# STM8L-FOX_80m_CNTL_V5_3.net
KiCad netlist of a schematic drawn in EAGLE
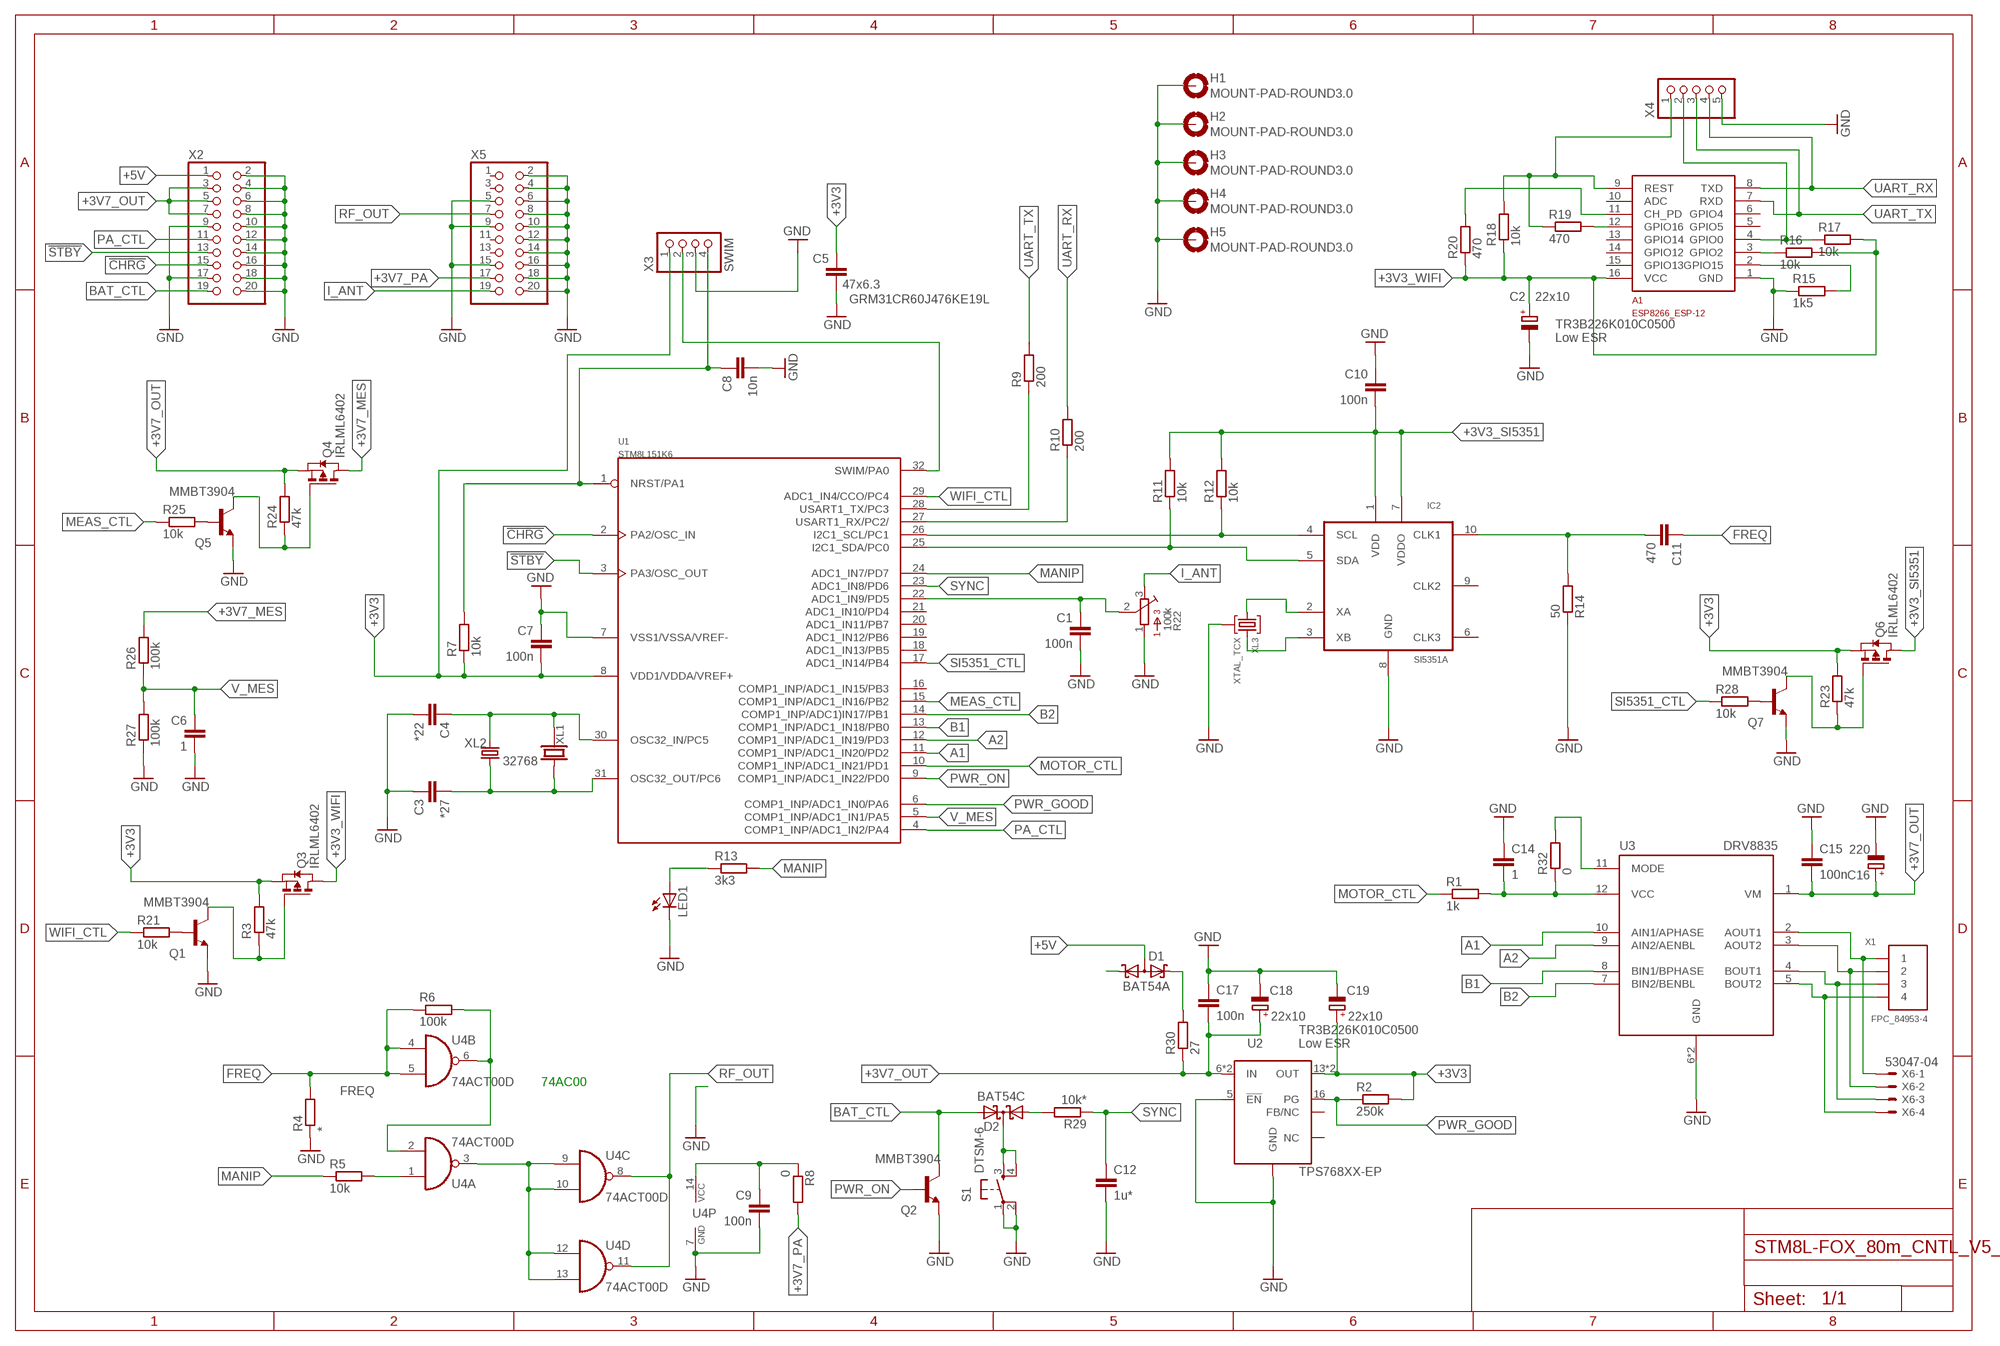
[diagram p0: schematic, sheet 1]

(export (version "E")
  (design (tool "Eeschema 10.0.6"))
  (components
    (comp (ref "A1")
      (value "ESP8266_ESP-12")
      (footprint "eagle-import:ESP8266-ESP12")
      (libsource (lib "eagle-import") (part "ESP8266_ESP-12"))
    )
    (comp (ref "C1")
      (value "100n")
      (footprint "eagle-import:C1206K")
      (libsource (lib "eagle-import") (part "C-EUC1206K"))
    )
    (comp (ref "C2")
      (value "22x10")
      (footprint "eagle-import:B_3528-21W")
      (libsource (lib "eagle-import") (part "CPOL-EUB/3528-21W"))
    )
    (comp (ref "C3")
      (value "*27")
      (footprint "eagle-import:C0805K")
      (libsource (lib "eagle-import") (part "C-EUC0805K"))
    )
    (comp (ref "C4")
      (value "*22")
      (footprint "eagle-import:C0805K")
      (libsource (lib "eagle-import") (part "C-EUC0805K"))
    )
    (comp (ref "C5")
      (value "47x6.3")
      (footprint "eagle-import:C1206K")
      (libsource (lib "eagle-import") (part "C-EUC1206K"))
    )
    (comp (ref "C6")
      (value "1")
      (footprint "eagle-import:C1206K")
      (libsource (lib "eagle-import") (part "C-EUC1206K"))
    )
    (comp (ref "C7")
      (value "100n")
      (footprint "eagle-import:C1206K")
      (libsource (lib "eagle-import") (part "C-EUC1206K"))
    )
    (comp (ref "C8")
      (value "10n")
      (footprint "eagle-import:C0805K")
      (libsource (lib "eagle-import") (part "C-EUC0805K"))
    )
    (comp (ref "C9")
      (value "100n")
      (footprint "eagle-import:C1206K")
      (libsource (lib "eagle-import") (part "C-EUC1206K"))
    )
    (comp (ref "C10")
      (value "100n")
      (footprint "eagle-import:C1206K")
      (libsource (lib "eagle-import") (part "C-EUC1206K"))
    )
    (comp (ref "C11")
      (value "470")
      (footprint "eagle-import:C1206K")
      (libsource (lib "eagle-import") (part "C-EUC1206K"))
    )
    (comp (ref "C12")
      (value "1u*")
      (footprint "eagle-import:C1206K")
      (libsource (lib "eagle-import") (part "C-EUC1206K"))
    )
    (comp (ref "C14")
      (value "1")
      (footprint "eagle-import:C1206K")
      (libsource (lib "eagle-import") (part "C-EUC1206K"))
    )
    (comp (ref "C15")
      (value "100n")
      (footprint "eagle-import:C1206K")
      (libsource (lib "eagle-import") (part "C-EUC1206K"))
    )
    (comp (ref "C16")
      (value "220")
      (footprint "eagle-import:C_6032-28R")
      (libsource (lib "eagle-import") (part "CPOL-EUC/6032-28R"))
    )
    (comp (ref "C17")
      (value "100n")
      (footprint "eagle-import:C1206K")
      (libsource (lib "eagle-import") (part "C-EUC1206K"))
    )
    (comp (ref "C18")
      (value "22x10")
      (footprint "eagle-import:B_3528-21W")
      (libsource (lib "eagle-import") (part "CPOL-EUB/3528-21W"))
    )
    (comp (ref "C19")
      (value "22x10")
      (footprint "eagle-import:B_3528-21W")
      (libsource (lib "eagle-import") (part "CPOL-EUB/3528-21W"))
    )
    (comp (ref "D1")
      (value "BAT54A")
      (footprint "eagle-import:SOT23")
      (libsource (lib "eagle-import") (part "BAT54A"))
    )
    (comp (ref "D2")
      (value "BAT54C")
      (footprint "eagle-import:SOT23")
      (libsource (lib "eagle-import") (part "BAT54C"))
    )
    (comp (ref "H1")
      (value "MOUNT-PAD-ROUND3.0")
      (footprint "eagle-import:3,0-PAD")
      (libsource (lib "eagle-import") (part "MOUNT-PAD-ROUND3.0"))
    )
    (comp (ref "H2")
      (value "MOUNT-PAD-ROUND3.0")
      (footprint "eagle-import:3,0-PAD")
      (libsource (lib "eagle-import") (part "MOUNT-PAD-ROUND3.0"))
    )
    (comp (ref "H3")
      (value "MOUNT-PAD-ROUND3.0")
      (footprint "eagle-import:3,0-PAD")
      (libsource (lib "eagle-import") (part "MOUNT-PAD-ROUND3.0"))
    )
    (comp (ref "H4")
      (value "MOUNT-PAD-ROUND3.0")
      (footprint "eagle-import:3,0-PAD")
      (libsource (lib "eagle-import") (part "MOUNT-PAD-ROUND3.0"))
    )
    (comp (ref "H5")
      (value "MOUNT-PAD-ROUND3.0")
      (footprint "eagle-import:3,0-PAD")
      (libsource (lib "eagle-import") (part "MOUNT-PAD-ROUND3.0"))
    )
    (comp (ref "IC2")
      (value "SI5351A")
      (footprint "eagle-import:MSOP10")
      (libsource (lib "eagle-import") (part "SI5351A"))
    )
    (comp (ref "LED1")
      (value "LED3MM")
      (footprint "eagle-import:LED3MM")
      (libsource (lib "eagle-import") (part "LED3MM"))
    )
    (comp (ref "Q1")
      (value "MMBT3904")
      (footprint "eagle-import:SOT23-BEC")
      (libsource (lib "eagle-import") (part "-NPN-SOT23-BECMMBT3904LT1"))
    )
    (comp (ref "Q2")
      (value "MMBT3904")
      (footprint "eagle-import:SOT23-BEC")
      (libsource (lib "eagle-import") (part "-NPN-SOT23-BECMMBT3904LT1"))
    )
    (comp (ref "Q3")
      (value "IRLML6402")
      (footprint "eagle-import:SOT-23")
      (libsource (lib "eagle-import") (part "IRLML6402"))
    )
    (comp (ref "Q4")
      (value "IRLML6402")
      (footprint "eagle-import:SOT-23")
      (libsource (lib "eagle-import") (part "IRLML6402"))
    )
    (comp (ref "Q5")
      (value "MMBT3904")
      (footprint "eagle-import:SOT23-BEC")
      (libsource (lib "eagle-import") (part "-NPN-SOT23-BECMMBT3904LT1"))
    )
    (comp (ref "Q6")
      (value "IRLML6402")
      (footprint "eagle-import:SOT-23")
      (libsource (lib "eagle-import") (part "IRLML6402"))
    )
    (comp (ref "Q7")
      (value "MMBT3904")
      (footprint "eagle-import:SOT23-BEC")
      (libsource (lib "eagle-import") (part "-NPN-SOT23-BECMMBT3904LT1"))
    )
    (comp (ref "R1")
      (value "1k")
      (footprint "eagle-import:R1206")
      (libsource (lib "eagle-import") (part "R-EU_R1206"))
    )
    (comp (ref "R2")
      (value "250k")
      (footprint "eagle-import:R1206")
      (libsource (lib "eagle-import") (part "R-EU_R1206"))
    )
    (comp (ref "R3")
      (value "47k")
      (footprint "eagle-import:R1206")
      (libsource (lib "eagle-import") (part "R-EU_R1206"))
    )
    (comp (ref "R4")
      (value "*")
      (footprint "eagle-import:R1206")
      (libsource (lib "eagle-import") (part "R-EU_R1206"))
    )
    (comp (ref "R5")
      (value "10k")
      (footprint "eagle-import:R1206")
      (libsource (lib "eagle-import") (part "R-EU_R1206"))
    )
    (comp (ref "R6")
      (value "100k")
      (footprint "eagle-import:R1206")
      (libsource (lib "eagle-import") (part "R-EU_R1206"))
    )
    (comp (ref "R7")
      (value "10k")
      (footprint "eagle-import:R1206")
      (libsource (lib "eagle-import") (part "R-EU_R1206"))
    )
    (comp (ref "R8")
      (value "0")
      (footprint "eagle-import:R1206")
      (libsource (lib "eagle-import") (part "R-EU_R1206"))
    )
    (comp (ref "R9")
      (value "200")
      (footprint "eagle-import:R1206")
      (libsource (lib "eagle-import") (part "R-EU_R1206"))
    )
    (comp (ref "R10")
      (value "200")
      (footprint "eagle-import:R1206")
      (libsource (lib "eagle-import") (part "R-EU_R1206"))
    )
    (comp (ref "R11")
      (value "10k")
      (footprint "eagle-import:R1206")
      (libsource (lib "eagle-import") (part "R-EU_R1206"))
    )
    (comp (ref "R12")
      (value "10k")
      (footprint "eagle-import:R1206")
      (libsource (lib "eagle-import") (part "R-EU_R1206"))
    )
    (comp (ref "R13")
      (value "3k3")
      (footprint "eagle-import:R1206")
      (libsource (lib "eagle-import") (part "R-EU_R1206"))
    )
    (comp (ref "R14")
      (value "50")
      (footprint "eagle-import:R1206")
      (libsource (lib "eagle-import") (part "R-EU_R1206"))
    )
    (comp (ref "R15")
      (value "1k5")
      (footprint "eagle-import:R1206")
      (libsource (lib "eagle-import") (part "R-EU_R1206"))
    )
    (comp (ref "R16")
      (value "10k")
      (footprint "eagle-import:R1206")
      (libsource (lib "eagle-import") (part "R-EU_R1206"))
    )
    (comp (ref "R17")
      (value "10k")
      (footprint "eagle-import:R1206")
      (libsource (lib "eagle-import") (part "R-EU_R1206"))
    )
    (comp (ref "R18")
      (value "10k")
      (footprint "eagle-import:R1206")
      (libsource (lib "eagle-import") (part "R-EU_R1206"))
    )
    (comp (ref "R19")
      (value "470")
      (footprint "eagle-import:R1206")
      (libsource (lib "eagle-import") (part "R-EU_R1206"))
    )
    (comp (ref "R20")
      (value "470")
      (footprint "eagle-import:R1206")
      (libsource (lib "eagle-import") (part "R-EU_R1206"))
    )
    (comp (ref "R21")
      (value "10k")
      (footprint "eagle-import:R1206")
      (libsource (lib "eagle-import") (part "R-EU_R1206"))
    )
    (comp (ref "R22")
      (value "100k")
      (footprint "eagle-import:3362R")
      (libsource (lib "eagle-import") (part "3362R"))
    )
    (comp (ref "R23")
      (value "47k")
      (footprint "eagle-import:R1206")
      (libsource (lib "eagle-import") (part "R-EU_R1206"))
    )
    (comp (ref "R24")
      (value "47k")
      (footprint "eagle-import:R1206")
      (libsource (lib "eagle-import") (part "R-EU_R1206"))
    )
    (comp (ref "R25")
      (value "10k")
      (footprint "eagle-import:R1206")
      (libsource (lib "eagle-import") (part "R-EU_R1206"))
    )
    (comp (ref "R26")
      (value "100k")
      (footprint "eagle-import:R1206")
      (libsource (lib "eagle-import") (part "R-EU_R1206"))
    )
    (comp (ref "R27")
      (value "100k")
      (footprint "eagle-import:R1206")
      (libsource (lib "eagle-import") (part "R-EU_R1206"))
    )
    (comp (ref "R28")
      (value "10k")
      (footprint "eagle-import:R1206")
      (libsource (lib "eagle-import") (part "R-EU_R1206"))
    )
    (comp (ref "R29")
      (value "10k*")
      (footprint "eagle-import:R1206")
      (libsource (lib "eagle-import") (part "R-EU_R1206"))
    )
    (comp (ref "R30")
      (value "27")
      (footprint "eagle-import:R1206")
      (libsource (lib "eagle-import") (part "R-EU_R1206"))
    )
    (comp (ref "R32")
      (value "0")
      (footprint "eagle-import:R1206")
      (libsource (lib "eagle-import") (part "R-EU_R1206"))
    )
    (comp (ref "S1")
      (value "DTSM-6")
      (footprint "eagle-import:DTSM-6")
      (libsource (lib "eagle-import") (part "DTSM-6"))
    )
    (comp (ref "U1")
      (value "STM8L151K6")
      (footprint "eagle-import:LQFP32-7X7")
      (libsource (lib "eagle-import") (part "STM8L151K6"))
    )
    (comp (ref "U2")
      (value "TPS768XX-EP")
      (footprint "eagle-import:TSSOP-20-PWP")
      (libsource (lib "eagle-import") (part "TPS768XX-EP"))
    )
    (comp (ref "U3")
      (value "DRV8835")
      (footprint "eagle-import:WSON_2X3")
      (libsource (lib "eagle-import") (part "DRV8835"))
    )
    (comp (ref "U4")
      (value "74ACT00D")
      (footprint "eagle-import:SO14")
      (libsource (lib "eagle-import") (part "7400DACT"))
    )
    (comp (ref "X1")
      (value "FPC_84953-4")
      (footprint "eagle-import:FPC_84953-4")
      (libsource (lib "eagle-import") (part "FPC_84953-4"))
    )
    (comp (ref "X2")
      (value "PINHD-2X10")
      (footprint "eagle-import:2X10")
      (libsource (lib "eagle-import") (part "PINHD-2X10"))
    )
    (comp (ref "X3")
      (value "SWIM")
      (footprint "eagle-import:1X04")
      (libsource (lib "eagle-import") (part "PINHD-1X4"))
    )
    (comp (ref "X4")
      (value "PINHD-1X5")
      (footprint "eagle-import:1X05")
      (libsource (lib "eagle-import") (part "PINHD-1X5"))
    )
    (comp (ref "X5")
      (value "PINHD-2X10")
      (footprint "eagle-import:2X10")
      (libsource (lib "eagle-import") (part "PINHD-2X10"))
    )
    (comp (ref "X6")
      (value "53047-04")
      (footprint "eagle-import:53047-04")
      (fields (field (name "MF") "WALDOM/MOLEX") (field (name "MPN") "53047-0410"))
      (libsource (lib "eagle-import") (part "53?-04047"))
    )
    (comp (ref "XL1")
      (value "CRYSTALSMD")
      (footprint "eagle-import:EPSON-MC146")
      (libsource (lib "eagle-import") (part "CRYSTALSMD"))
    )
    (comp (ref "XL2")
      (value "32768")
      (footprint "eagle-import:TC38H-PCB")
      (libsource (lib "eagle-import") (part "CRYSTALTC38H-PCB"))
    )
    (comp (ref "XL3")
      (value "XTAL_TCX")
      (footprint "eagle-import:TXC")
      (libsource (lib "eagle-import") (part "XTAL_TCX"))
    )
  )
  (nets
    (net (code "1") (name "+3V3") (class "Default")
      (node (ref "C19") (pin "+") (pinfunction "+_+") (pintype "passive"))
      (node (ref "C5") (pin "2") (pinfunction "2_2") (pintype "passive"))
      (node (ref "C7") (pin "1") (pinfunction "1_1") (pintype "passive"))
      (node (ref "Q3") (pin "2") (pinfunction "S_2") (pintype "passive"))
      (node (ref "Q6") (pin "2") (pinfunction "S_2") (pintype "passive"))
      (node (ref "R2") (pin "2") (pinfunction "2_2") (pintype "passive"))
      (node (ref "R23") (pin "2") (pinfunction "2_2") (pintype "passive"))
      (node (ref "R3") (pin "2") (pinfunction "2_2") (pintype "passive"))
      (node (ref "R7") (pin "1") (pinfunction "1_1") (pintype "passive"))
      (node (ref "U1") (pin "8") (pinfunction "VDD1/VDDA/VREF+_8") (pintype "bidirectional"))
      (node (ref "U2") (pin "13") (pinfunction "OUT_13") (pintype "output"))
      (node (ref "U2") (pin "14") (pinfunction "OUT_14") (pintype "output"))
      (node (ref "X3") (pin "1") (pinfunction "1_1") (pintype "passive"))
    )
    (net (code "2") (name "+3V3_SI5351") (class "Default")
      (node (ref "C10") (pin "1") (pinfunction "1_1") (pintype "passive"))
      (node (ref "IC2") (pin "1") (pinfunction "VDD_1") (pintype "bidirectional"))
      (node (ref "IC2") (pin "7") (pinfunction "VDDO_7") (pintype "bidirectional"))
      (node (ref "Q6") (pin "3") (pinfunction "D_3") (pintype "passive"))
      (node (ref "R11") (pin "2") (pinfunction "2_2") (pintype "passive"))
      (node (ref "R12") (pin "2") (pinfunction "2_2") (pintype "passive"))
    )
    (net (code "3") (name "+3V3_WIFI") (class "Default")
      (node (ref "A1") (pin "16") (pinfunction "VCC_16") (pintype "bidirectional"))
      (node (ref "C2") (pin "+") (pinfunction "+_+") (pintype "passive"))
      (node (ref "Q3") (pin "3") (pinfunction "D_3") (pintype "passive"))
      (node (ref "R16") (pin "2") (pinfunction "2_2") (pintype "passive"))
      (node (ref "R17") (pin "2") (pinfunction "2_2") (pintype "passive"))
      (node (ref "R18") (pin "1") (pinfunction "1_1") (pintype "passive"))
      (node (ref "R20") (pin "1") (pinfunction "1_1") (pintype "passive"))
    )
    (net (code "4") (name "+3V7_MES") (class "Default")
      (node (ref "Q4") (pin "3") (pinfunction "D_3") (pintype "passive"))
      (node (ref "R26") (pin "2") (pinfunction "2_2") (pintype "passive"))
    )
    (net (code "5") (name "+3V7_OUT") (class "Default")
      (node (ref "C15") (pin "2") (pinfunction "2_2") (pintype "passive"))
      (node (ref "C16") (pin "+") (pinfunction "+_+") (pintype "passive"))
      (node (ref "C17") (pin "2") (pinfunction "2_2") (pintype "passive"))
      (node (ref "C18") (pin "+") (pinfunction "+_+") (pintype "passive"))
      (node (ref "Q4") (pin "2") (pinfunction "S_2") (pintype "passive"))
      (node (ref "R24") (pin "2") (pinfunction "2_2") (pintype "passive"))
      (node (ref "R30") (pin "1") (pinfunction "1_1") (pintype "passive"))
      (node (ref "U2") (pin "6") (pinfunction "IN_6") (pintype "input"))
      (node (ref "U2") (pin "7") (pinfunction "IN_7") (pintype "input"))
      (node (ref "U3") (pin "1") (pinfunction "VM_1") (pintype "bidirectional"))
      (node (ref "X2") (pin "3") (pinfunction "3_3") (pintype "passive"))
      (node (ref "X2") (pin "5") (pinfunction "5_5") (pintype "passive"))
      (node (ref "X2") (pin "7") (pinfunction "7_7") (pintype "passive"))
    )
    (net (code "6") (name "+3V7_PA") (class "Default")
      (node (ref "R8") (pin "2") (pinfunction "2_2") (pintype "passive"))
      (node (ref "X5") (pin "17") (pinfunction "17_17") (pintype "passive"))
    )
    (net (code "7") (name "+5V") (class "Default")
      (node (ref "D1") (pin "3") (pinfunction "AA_3") (pintype "passive"))
      (node (ref "X2") (pin "1") (pinfunction "1_1") (pintype "passive"))
    )
    (net (code "8") (name "/~{CHRG}") (class "Default")
      (node (ref "U1") (pin "2") (pinfunction "PA2/OSC_IN_2") (pintype "bidirectional"))
      (node (ref "X2") (pin "15") (pinfunction "15_15") (pintype "passive"))
    )
    (net (code "9") (name "/~{STBY}") (class "Default")
      (node (ref "U1") (pin "3") (pinfunction "PA3/OSC_OUT_3") (pintype "bidirectional"))
      (node (ref "X2") (pin "13") (pinfunction "13_13") (pintype "passive"))
    )
    (net (code "10") (name "A1") (class "Default")
      (node (ref "U1") (pin "11") (pinfunction "COMP1_INP/ADC1_IN20/PD2_11") (pintype "bidirectional"))
      (node (ref "U3") (pin "10") (pinfunction "AIN1/APHASE_10") (pintype "bidirectional"))
    )
    (net (code "11") (name "A2") (class "Default")
      (node (ref "U1") (pin "12") (pinfunction "COMP1_INP/ADC1_IN19/PD3_12") (pintype "bidirectional"))
      (node (ref "U3") (pin "9") (pinfunction "AIN2/AENBL_9") (pintype "bidirectional"))
    )
    (net (code "12") (name "B1") (class "Default")
      (node (ref "U1") (pin "13") (pinfunction "COMP1_INP/ADC1_IN18/PB0_13") (pintype "bidirectional"))
      (node (ref "U3") (pin "8") (pinfunction "BIN1/BPHASE_8") (pintype "bidirectional"))
    )
    (net (code "13") (name "B2") (class "Default")
      (node (ref "U1") (pin "14") (pinfunction "COMP1_INP/ADC1)IN17/PB1_14") (pintype "bidirectional"))
      (node (ref "U3") (pin "7") (pinfunction "BIN2/BENBL_7") (pintype "bidirectional"))
    )
    (net (code "14") (name "BAT_CTL") (class "Default")
      (node (ref "D2") (pin "2") (pinfunction "A2_2") (pintype "passive"))
      (node (ref "Q2") (pin "C") (pinfunction "C_C") (pintype "passive"))
      (node (ref "X2") (pin "19") (pinfunction "19_19") (pintype "passive"))
    )
    (net (code "15") (name "FREQ") (class "Default")
      (node (ref "C11") (pin "1") (pinfunction "1_1") (pintype "passive"))
      (node (ref "R4") (pin "2") (pinfunction "2_2") (pintype "passive"))
      (node (ref "R6") (pin "1") (pinfunction "1_1") (pintype "passive"))
      (node (ref "U4") (pin "4") (pinfunction "I0_4") (pintype "input"))
      (node (ref "U4") (pin "5") (pinfunction "I1_5") (pintype "input"))
    )
    (net (code "16") (name "GND") (class "Default")
      (node (ref "A1") (pin "1") (pinfunction "GND_1") (pintype "bidirectional"))
      (node (ref "C1") (pin "1") (pinfunction "1_1") (pintype "passive"))
      (node (ref "C10") (pin "2") (pinfunction "2_2") (pintype "passive"))
      (node (ref "C12") (pin "2") (pinfunction "2_2") (pintype "passive"))
      (node (ref "C14") (pin "1") (pinfunction "1_1") (pintype "passive"))
      (node (ref "C15") (pin "1") (pinfunction "1_1") (pintype "passive"))
      (node (ref "C16") (pin "-") (pinfunction "-_-") (pintype "passive"))
      (node (ref "C17") (pin "1") (pinfunction "1_1") (pintype "passive"))
      (node (ref "C18") (pin "-") (pinfunction "-_-") (pintype "passive"))
      (node (ref "C19") (pin "-") (pinfunction "-_-") (pintype "passive"))
      (node (ref "C2") (pin "-") (pinfunction "-_-") (pintype "passive"))
      (node (ref "C3") (pin "1") (pinfunction "1_1") (pintype "passive"))
      (node (ref "C4") (pin "2") (pinfunction "2_2") (pintype "passive"))
      (node (ref "C5") (pin "1") (pinfunction "1_1") (pintype "passive"))
      (node (ref "C6") (pin "2") (pinfunction "2_2") (pintype "passive"))
      (node (ref "C7") (pin "2") (pinfunction "2_2") (pintype "passive"))
      (node (ref "C8") (pin "2") (pinfunction "2_2") (pintype "passive"))
      (node (ref "C9") (pin "2") (pinfunction "2_2") (pintype "passive"))
      (node (ref "H1") (pin "B3,0") (pinfunction "MOUNT_B3,0") (pintype "passive"))
      (node (ref "H2") (pin "B3,0") (pinfunction "MOUNT_B3,0") (pintype "passive"))
      (node (ref "H3") (pin "B3,0") (pinfunction "MOUNT_B3,0") (pintype "passive"))
      (node (ref "H4") (pin "B3,0") (pinfunction "MOUNT_B3,0") (pintype "passive"))
      (node (ref "H5") (pin "B3,0") (pinfunction "MOUNT_B3,0") (pintype "passive"))
      (node (ref "IC2") (pin "8") (pinfunction "GND_8") (pintype "bidirectional"))
      (node (ref "LED1") (pin "K") (pinfunction "C_K") (pintype "passive"))
      (node (ref "Q1") (pin "E") (pinfunction "E_E") (pintype "passive"))
      (node (ref "Q2") (pin "E") (pinfunction "E_E") (pintype "passive"))
      (node (ref "Q5") (pin "E") (pinfunction "E_E") (pintype "passive"))
      (node (ref "Q7") (pin "E") (pinfunction "E_E") (pintype "passive"))
      (node (ref "R14") (pin "1") (pinfunction "1_1") (pintype "passive"))
      (node (ref "R15") (pin "1") (pinfunction "1_1") (pintype "passive"))
      (node (ref "R22") (pin "1") (pinfunction "1_1") (pintype "passive"))
      (node (ref "R27") (pin "1") (pinfunction "1_1") (pintype "passive"))
      (node (ref "R4") (pin "1") (pinfunction "1_1") (pintype "passive"))
      (node (ref "S1") (pin "1") (pinfunction "1_1") (pintype "passive"))
      (node (ref "S1") (pin "2") (pinfunction "2_2") (pintype "passive"))
      (node (ref "U1") (pin "7") (pinfunction "VSS1/VSSA/VREF-_7") (pintype "bidirectional"))
      (node (ref "U2") (pin "1") (pinfunction "GND_1") (pintype "bidirectional"))
      (node (ref "U2") (pin "10") (pinfunction "GND_10") (pintype "bidirectional"))
      (node (ref "U2") (pin "11") (pinfunction "GND_11") (pintype "bidirectional"))
      (node (ref "U2") (pin "12") (pinfunction "GND_12") (pintype "bidirectional"))
      (node (ref "U2") (pin "19") (pinfunction "GND_19") (pintype "bidirectional"))
      (node (ref "U2") (pin "2") (pinfunction "GND_2") (pintype "bidirectional"))
      (node (ref "U2") (pin "20") (pinfunction "GND_20") (pintype "bidirectional"))
      (node (ref "U2") (pin "3") (pinfunction "GND_3") (pintype "bidirectional"))
      (node (ref "U2") (pin "5") (pinfunction "~{EN}_5") (pintype "input"))
      (node (ref "U2") (pin "9") (pinfunction "GND_9") (pintype "bidirectional"))
      (node (ref "U2") (pin "PAD") (pinfunction "GND_PAD") (pintype "bidirectional"))
      (node (ref "U3") (pin "6") (pinfunction "GND_6") (pintype "bidirectional"))
      (node (ref "U3") (pin "PAD") (pinfunction "GND_PAD") (pintype "bidirectional"))
      (node (ref "U4") (pin "7") (pinfunction "GND_7") (pintype "power_in"))
      (node (ref "X2") (pin "10") (pinfunction "10_10") (pintype "passive"))
      (node (ref "X2") (pin "12") (pinfunction "12_12") (pintype "passive"))
      (node (ref "X2") (pin "14") (pinfunction "14_14") (pintype "passive"))
      (node (ref "X2") (pin "16") (pinfunction "16_16") (pintype "passive"))
      (node (ref "X2") (pin "17") (pinfunction "17_17") (pintype "passive"))
      (node (ref "X2") (pin "18") (pinfunction "18_18") (pintype "passive"))
      (node (ref "X2") (pin "2") (pinfunction "2_2") (pintype "passive"))
      (node (ref "X2") (pin "20") (pinfunction "20_20") (pintype "passive"))
      (node (ref "X2") (pin "4") (pinfunction "4_4") (pintype "passive"))
      (node (ref "X2") (pin "6") (pinfunction "6_6") (pintype "passive"))
      (node (ref "X2") (pin "8") (pinfunction "8_8") (pintype "passive"))
      (node (ref "X2") (pin "9") (pinfunction "9_9") (pintype "passive"))
      (node (ref "X3") (pin "3") (pinfunction "3_3") (pintype "passive"))
      (node (ref "X4") (pin "5") (pinfunction "5_5") (pintype "passive"))
      (node (ref "X5") (pin "10") (pinfunction "10_10") (pintype "passive"))
      (node (ref "X5") (pin "12") (pinfunction "12_12") (pintype "passive"))
      (node (ref "X5") (pin "14") (pinfunction "14_14") (pintype "passive"))
      (node (ref "X5") (pin "15") (pinfunction "15_15") (pintype "passive"))
      (node (ref "X5") (pin "16") (pinfunction "16_16") (pintype "passive"))
      (node (ref "X5") (pin "18") (pinfunction "18_18") (pintype "passive"))
      (node (ref "X5") (pin "2") (pinfunction "2_2") (pintype "passive"))
      (node (ref "X5") (pin "20") (pinfunction "20_20") (pintype "passive"))
      (node (ref "X5") (pin "4") (pinfunction "4_4") (pintype "passive"))
      (node (ref "X5") (pin "5") (pinfunction "5_5") (pintype "passive"))
      (node (ref "X5") (pin "6") (pinfunction "6_6") (pintype "passive"))
      (node (ref "X5") (pin "8") (pinfunction "8_8") (pintype "passive"))
      (node (ref "X5") (pin "9") (pinfunction "9_9") (pintype "passive"))
      (node (ref "XL3") (pin "2") (pinfunction "2_2") (pintype "passive"))
      (node (ref "XL3") (pin "4") (pinfunction "2_4") (pintype "passive"))
    )
    (net (code "17") (name "I_ANT") (class "Default")
      (node (ref "R22") (pin "3") (pinfunction "3_3") (pintype "passive"))
      (node (ref "X5") (pin "19") (pinfunction "19_19") (pintype "passive"))
    )
    (net (code "18") (name "MANIP") (class "Default")
      (node (ref "R13") (pin "2") (pinfunction "2_2") (pintype "passive"))
      (node (ref "R5") (pin "1") (pinfunction "1_1") (pintype "passive"))
      (node (ref "U1") (pin "24") (pinfunction "ADC1_IN7/PD7_24") (pintype "bidirectional"))
    )
    (net (code "19") (name "MEAS_CTL") (class "Default")
      (node (ref "R25") (pin "1") (pinfunction "1_1") (pintype "passive"))
      (node (ref "U1") (pin "15") (pinfunction "COMP1_INP/ADC1_IN16/PB2_15") (pintype "bidirectional"))
    )
    (net (code "20") (name "MOTOR_CTL") (class "Default")
      (node (ref "R1") (pin "1") (pinfunction "1_1") (pintype "passive"))
      (node (ref "U1") (pin "10") (pinfunction "COMP1_INP/ADC1_IN21/PD1_10") (pintype "bidirectional"))
    )
    (net (code "21") (name "Net-(A1-CH_PD)") (class "Default")
      (node (ref "A1") (pin "11") (pinfunction "CH_PD_11") (pintype "bidirectional"))
      (node (ref "R20") (pin "2") (pinfunction "2_2") (pintype "passive"))
    )
    (net (code "22") (name "Net-(A1-GPIO0)") (class "Default")
      (node (ref "A1") (pin "4") (pinfunction "GPIO0_4") (pintype "bidirectional"))
      (node (ref "R17") (pin "1") (pinfunction "1_1") (pintype "passive"))
      (node (ref "X4") (pin "2") (pinfunction "2_2") (pintype "passive"))
    )
    (net (code "23") (name "Net-(A1-GPIO2)") (class "Default")
      (node (ref "A1") (pin "3") (pinfunction "GPIO2_3") (pintype "bidirectional"))
      (node (ref "R16") (pin "1") (pinfunction "1_1") (pintype "passive"))
    )
    (net (code "24") (name "Net-(A1-GPIO15)") (class "Default")
      (node (ref "A1") (pin "2") (pinfunction "GPIO15_2") (pintype "bidirectional"))
      (node (ref "R15") (pin "2") (pinfunction "2_2") (pintype "passive"))
    )
    (net (code "25") (name "Net-(A1-GPIO16)") (class "Default")
      (node (ref "A1") (pin "12") (pinfunction "GPIO16_12") (pintype "bidirectional"))
      (node (ref "R19") (pin "2") (pinfunction "2_2") (pintype "passive"))
    )
    (net (code "26") (name "Net-(A1-REST)") (class "Default")
      (node (ref "A1") (pin "9") (pinfunction "REST_9") (pintype "bidirectional"))
      (node (ref "R18") (pin "2") (pinfunction "2_2") (pintype "passive"))
      (node (ref "R19") (pin "1") (pinfunction "1_1") (pintype "passive"))
      (node (ref "X4") (pin "1") (pinfunction "1_1") (pintype "passive"))
    )
    (net (code "27") (name "Net-(D1-K2)") (class "Default")
      (node (ref "D1") (pin "2") (pinfunction "K2_2") (pintype "passive"))
      (node (ref "R30") (pin "2") (pinfunction "2_2") (pintype "passive"))
    )
    (net (code "28") (name "Net-(D2-A1)") (class "Default")
      (node (ref "D2") (pin "1") (pinfunction "A1_1") (pintype "passive"))
      (node (ref "R29") (pin "2") (pinfunction "2_2") (pintype "passive"))
    )
    (net (code "29") (name "Net-(D2-CC)") (class "Default")
      (node (ref "D2") (pin "3") (pinfunction "CC_3") (pintype "passive"))
      (node (ref "S1") (pin "3") (pinfunction "3_3") (pintype "passive"))
      (node (ref "S1") (pin "4") (pinfunction "4_4") (pintype "passive"))
    )
    (net (code "30") (name "Net-(IC2-CLK1)") (class "Default")
      (node (ref "C11") (pin "2") (pinfunction "2_2") (pintype "passive"))
      (node (ref "IC2") (pin "10") (pinfunction "CLK1_10") (pintype "bidirectional"))
      (node (ref "R14") (pin "2") (pinfunction "2_2") (pintype "passive"))
    )
    (net (code "31") (name "Net-(IC2-SCL)") (class "Default")
      (node (ref "IC2") (pin "4") (pinfunction "SCL_4") (pintype "bidirectional"))
      (node (ref "R12") (pin "1") (pinfunction "1_1") (pintype "passive"))
      (node (ref "U1") (pin "26") (pinfunction "I2C1_SCL/PC1_26") (pintype "bidirectional"))
    )
    (net (code "32") (name "Net-(IC2-SDA)") (class "Default")
      (node (ref "IC2") (pin "5") (pinfunction "SDA_5") (pintype "bidirectional"))
      (node (ref "R11") (pin "1") (pinfunction "1_1") (pintype "passive"))
      (node (ref "U1") (pin "25") (pinfunction "I2C1_SDA/PC0_25") (pintype "bidirectional"))
    )
    (net (code "33") (name "Net-(IC2-XA)") (class "Default")
      (node (ref "IC2") (pin "2") (pinfunction "XA_2") (pintype "bidirectional"))
      (node (ref "XL3") (pin "1") (pinfunction "1_1") (pintype "passive"))
    )
    (net (code "34") (name "Net-(IC2-XB)") (class "Default")
      (node (ref "IC2") (pin "3") (pinfunction "XB_3") (pintype "bidirectional"))
      (node (ref "XL3") (pin "3") (pinfunction "3_3") (pintype "passive"))
    )
    (net (code "35") (name "Net-(LED1-PadA)") (class "Default")
      (node (ref "LED1") (pin "A") (pinfunction "A_A") (pintype "passive"))
      (node (ref "R13") (pin "1") (pinfunction "1_1") (pintype "passive"))
    )
    (net (code "36") (name "Net-(Q1-PadB)") (class "Default")
      (node (ref "Q1") (pin "B") (pinfunction "B_B") (pintype "passive"))
      (node (ref "R21") (pin "2") (pinfunction "2_2") (pintype "passive"))
    )
    (net (code "37") (name "Net-(Q3-G)") (class "Default")
      (node (ref "Q1") (pin "C") (pinfunction "C_C") (pintype "passive"))
      (node (ref "Q3") (pin "1") (pinfunction "G_1") (pintype "passive"))
      (node (ref "R3") (pin "1") (pinfunction "1_1") (pintype "passive"))
    )
    (net (code "38") (name "Net-(Q4-G)") (class "Default")
      (node (ref "Q4") (pin "1") (pinfunction "G_1") (pintype "passive"))
      (node (ref "Q5") (pin "C") (pinfunction "C_C") (pintype "passive"))
      (node (ref "R24") (pin "1") (pinfunction "1_1") (pintype "passive"))
    )
    (net (code "39") (name "Net-(Q5-PadB)") (class "Default")
      (node (ref "Q5") (pin "B") (pinfunction "B_B") (pintype "passive"))
      (node (ref "R25") (pin "2") (pinfunction "2_2") (pintype "passive"))
    )
    (net (code "40") (name "Net-(Q6-G)") (class "Default")
      (node (ref "Q6") (pin "1") (pinfunction "G_1") (pintype "passive"))
      (node (ref "Q7") (pin "C") (pinfunction "C_C") (pintype "passive"))
      (node (ref "R23") (pin "1") (pinfunction "1_1") (pintype "passive"))
    )
    (net (code "41") (name "Net-(Q7-PadB)") (class "Default")
      (node (ref "Q7") (pin "B") (pinfunction "B_B") (pintype "passive"))
      (node (ref "R28") (pin "2") (pinfunction "2_2") (pintype "passive"))
    )
    (net (code "42") (name "Net-(U1-ADC1_IN9{slash}PD5)") (class "Default")
      (node (ref "C1") (pin "2") (pinfunction "2_2") (pintype "passive"))
      (node (ref "R22") (pin "2") (pinfunction "2_2") (pintype "passive"))
      (node (ref "U1") (pin "22") (pinfunction "ADC1_IN9/PD5_22") (pintype "bidirectional"))
    )
    (net (code "43") (name "Net-(U1-NRST{slash}PA1)") (class "Default")
      (node (ref "C8") (pin "1") (pinfunction "1_1") (pintype "passive"))
      (node (ref "R7") (pin "2") (pinfunction "2_2") (pintype "passive"))
      (node (ref "U1") (pin "1") (pinfunction "NRST/PA1_1") (pintype "bidirectional"))
      (node (ref "X3") (pin "4") (pinfunction "4_4") (pintype "passive"))
    )
    (net (code "44") (name "Net-(U1-OSC32_IN{slash}PC5)") (class "Default")
      (node (ref "C4") (pin "1") (pinfunction "1_1") (pintype "passive"))
      (node (ref "U1") (pin "30") (pinfunction "OSC32_IN/PC5_30") (pintype "bidirectional"))
      (node (ref "XL1") (pin "P$1") (pinfunction "1_P$1") (pintype "passive"))
      (node (ref "XL2") (pin "P$2") (pinfunction "2_P$2") (pintype "passive"))
    )
    (net (code "45") (name "Net-(U1-OSC32_OUT{slash}PC6)") (class "Default")
      (node (ref "C3") (pin "2") (pinfunction "2_2") (pintype "passive"))
      (node (ref "U1") (pin "31") (pinfunction "OSC32_OUT/PC6_31") (pintype "bidirectional"))
      (node (ref "XL1") (pin "P$2") (pinfunction "2_P$2") (pintype "passive"))
      (node (ref "XL2") (pin "P$1") (pinfunction "1_P$1") (pintype "passive"))
    )
    (net (code "46") (name "Net-(U1-SWIM{slash}PA0)") (class "Default")
      (node (ref "U1") (pin "32") (pinfunction "SWIM/PA0_32") (pintype "bidirectional"))
      (node (ref "X3") (pin "2") (pinfunction "2_2") (pintype "passive"))
    )
    (net (code "47") (name "Net-(U1-USART1_RX{slash}PC2{slash})") (class "Default")
      (node (ref "R10") (pin "1") (pinfunction "1_1") (pintype "passive"))
      (node (ref "U1") (pin "27") (pinfunction "USART1_RX/PC2/_27") (pintype "bidirectional"))
    )
    (net (code "48") (name "Net-(U1-USART1_TX{slash}PC3)") (class "Default")
      (node (ref "R9") (pin "1") (pinfunction "1_1") (pintype "passive"))
      (node (ref "U1") (pin "28") (pinfunction "USART1_TX/PC3_28") (pintype "bidirectional"))
    )
    (net (code "49") (name "Net-(U3-AOUT1)") (class "Default")
      (node (ref "U3") (pin "2") (pinfunction "AOUT1_2") (pintype "bidirectional"))
      (node (ref "X1") (pin "1") (pinfunction "1_1") (pintype "bidirectional"))
      (node (ref "X6") (pin "1") (pinfunction "S_1") (pintype "passive"))
    )
    (net (code "50") (name "Net-(U3-AOUT2)") (class "Default")
      (node (ref "U3") (pin "3") (pinfunction "AOUT2_3") (pintype "bidirectional"))
      (node (ref "X1") (pin "2") (pinfunction "2_2") (pintype "bidirectional"))
      (node (ref "X6") (pin "2") (pinfunction "S_2") (pintype "passive"))
    )
    (net (code "51") (name "Net-(U3-BOUT1)") (class "Default")
      (node (ref "U3") (pin "4") (pinfunction "BOUT1_4") (pintype "bidirectional"))
      (node (ref "X1") (pin "3") (pinfunction "3_3") (pintype "bidirectional"))
      (node (ref "X6") (pin "3") (pinfunction "S_3") (pintype "passive"))
    )
    (net (code "52") (name "Net-(U3-BOUT2)") (class "Default")
      (node (ref "U3") (pin "5") (pinfunction "BOUT2_5") (pintype "bidirectional"))
      (node (ref "X1") (pin "4") (pinfunction "4_4") (pintype "bidirectional"))
      (node (ref "X6") (pin "4") (pinfunction "S_4") (pintype "passive"))
    )
    (net (code "53") (name "Net-(U3-MODE)") (class "Default")
      (node (ref "R32") (pin "2") (pinfunction "2_2") (pintype "passive"))
      (node (ref "U3") (pin "11") (pinfunction "MODE_11") (pintype "bidirectional"))
    )
    (net (code "54") (name "Net-(U3-VCC)") (class "Default")
      (node (ref "C14") (pin "2") (pinfunction "2_2") (pintype "passive"))
      (node (ref "R1") (pin "2") (pinfunction "2_2") (pintype "passive"))
      (node (ref "R32") (pin "1") (pinfunction "1_1") (pintype "passive"))
      (node (ref "U3") (pin "12") (pinfunction "VCC_12") (pintype "bidirectional"))
    )
    (net (code "55") (name "Net-(U4A-I0)") (class "Default")
      (node (ref "R5") (pin "2") (pinfunction "2_2") (pintype "passive"))
      (node (ref "U4") (pin "1") (pinfunction "I0_1") (pintype "input"))
    )
    (net (code "56") (name "Net-(U4A-I1)") (class "Default")
      (node (ref "R6") (pin "2") (pinfunction "2_2") (pintype "passive"))
      (node (ref "U4") (pin "2") (pinfunction "I1_2") (pintype "input"))
      (node (ref "U4") (pin "6") (pinfunction "O_6") (pintype "output"))
    )
    (net (code "57") (name "Net-(U4A-O)") (class "Default")
      (node (ref "U4") (pin "10") (pinfunction "I1_10") (pintype "input"))
      (node (ref "U4") (pin "12") (pinfunction "I0_12") (pintype "input"))
      (node (ref "U4") (pin "13") (pinfunction "I1_13") (pintype "input"))
      (node (ref "U4") (pin "3") (pinfunction "O_3") (pintype "output"))
      (node (ref "U4") (pin "9") (pinfunction "I0_9") (pintype "input"))
    )
    (net (code "58") (name "Net-(U4E-VCC)") (class "Default")
      (node (ref "C9") (pin "1") (pinfunction "1_1") (pintype "passive"))
      (node (ref "R8") (pin "1") (pinfunction "1_1") (pintype "passive"))
      (node (ref "U4") (pin "14") (pinfunction "VCC_14") (pintype "power_in"))
    )
    (net (code "59") (name "PA_CTL") (class "Default")
      (node (ref "U1") (pin "4") (pinfunction "COMP1_INP/ADC1_IN2/PA4_4") (pintype "bidirectional"))
      (node (ref "X2") (pin "11") (pinfunction "11_11") (pintype "passive"))
    )
    (net (code "60") (name "PWR_GOOD") (class "Default")
      (node (ref "R2") (pin "1") (pinfunction "1_1") (pintype "passive"))
      (node (ref "U1") (pin "6") (pinfunction "COMP1_INP/ADC1_IN0/PA6_6") (pintype "bidirectional"))
      (node (ref "U2") (pin "16") (pinfunction "PG_16") (pintype "bidirectional"))
    )
    (net (code "61") (name "PWR_ON") (class "Default")
      (node (ref "Q2") (pin "B") (pinfunction "B_B") (pintype "passive"))
      (node (ref "U1") (pin "9") (pinfunction "COMP1_INP/ADC1_IN22/PD0_9") (pintype "bidirectional"))
    )
    (net (code "62") (name "RF_OUT") (class "Default")
      (node (ref "U4") (pin "11") (pinfunction "O_11") (pintype "output"))
      (node (ref "U4") (pin "8") (pinfunction "O_8") (pintype "output"))
      (node (ref "X5") (pin "7") (pinfunction "7_7") (pintype "passive"))
    )
    (net (code "63") (name "SI5351_CTL") (class "Default")
      (node (ref "R28") (pin "1") (pinfunction "1_1") (pintype "passive"))
      (node (ref "U1") (pin "17") (pinfunction "ADC1_IN14/PB4_17") (pintype "bidirectional"))
    )
    (net (code "64") (name "SYNC") (class "Default")
      (node (ref "C12") (pin "1") (pinfunction "1_1") (pintype "passive"))
      (node (ref "R29") (pin "1") (pinfunction "1_1") (pintype "passive"))
      (node (ref "U1") (pin "23") (pinfunction "ADC1_IN8/PD6_23") (pintype "bidirectional"))
    )
    (net (code "65") (name "UART_RX") (class "Default")
      (node (ref "A1") (pin "8") (pinfunction "TXD_8") (pintype "bidirectional"))
      (node (ref "R10") (pin "2") (pinfunction "2_2") (pintype "passive"))
      (node (ref "X4") (pin "4") (pinfunction "4_4") (pintype "passive"))
    )
    (net (code "66") (name "UART_TX") (class "Default")
      (node (ref "A1") (pin "7") (pinfunction "RXD_7") (pintype "bidirectional"))
      (node (ref "R9") (pin "2") (pinfunction "2_2") (pintype "passive"))
      (node (ref "X4") (pin "3") (pinfunction "3_3") (pintype "passive"))
    )
    (net (code "67") (name "V_MES") (class "Default")
      (node (ref "C6") (pin "1") (pinfunction "1_1") (pintype "passive"))
      (node (ref "R26") (pin "1") (pinfunction "1_1") (pintype "passive"))
      (node (ref "R27") (pin "2") (pinfunction "2_2") (pintype "passive"))
      (node (ref "U1") (pin "5") (pinfunction "COMP1_INP/ADC1_IN1/PA5_5") (pintype "bidirectional"))
    )
    (net (code "68") (name "WIFI_CTL") (class "Default")
      (node (ref "R21") (pin "1") (pinfunction "1_1") (pintype "passive"))
      (node (ref "U1") (pin "29") (pinfunction "ADC1_IN4/CCO/PC4_29") (pintype "bidirectional"))
    )
    (net (code "69") (name "unconnected-(A1-ADC-Pad10)") (class "Default")
      (node (ref "A1") (pin "10") (pinfunction "ADC_10") (pintype "bidirectional"))
    )
    (net (code "70") (name "unconnected-(A1-GPIO4-Pad6)") (class "Default")
      (node (ref "A1") (pin "6") (pinfunction "GPIO4_6") (pintype "bidirectional"))
    )
    (net (code "71") (name "unconnected-(A1-GPIO5-Pad5)") (class "Default")
      (node (ref "A1") (pin "5") (pinfunction "GPIO5_5") (pintype "bidirectional"))
    )
    (net (code "72") (name "unconnected-(A1-GPIO12-Pad14)") (class "Default")
      (node (ref "A1") (pin "14") (pinfunction "GPIO12_14") (pintype "bidirectional"))
    )
    (net (code "73") (name "unconnected-(A1-GPIO13-Pad15)") (class "Default")
      (node (ref "A1") (pin "15") (pinfunction "GPIO13_15") (pintype "bidirectional"))
    )
    (net (code "74") (name "unconnected-(A1-GPIO14-Pad13)") (class "Default")
      (node (ref "A1") (pin "13") (pinfunction "GPIO14_13") (pintype "bidirectional"))
    )
    (net (code "75") (name "unconnected-(D1-K1-Pad1)") (class "Default")
      (node (ref "D1") (pin "1") (pinfunction "K1_1") (pintype "passive"))
    )
    (net (code "76") (name "unconnected-(IC2-CLK2-Pad9)") (class "Default")
      (node (ref "IC2") (pin "9") (pinfunction "CLK2_9") (pintype "bidirectional"))
    )
    (net (code "77") (name "unconnected-(IC2-CLK3-Pad6)") (class "Default")
      (node (ref "IC2") (pin "6") (pinfunction "CLK3_6") (pintype "bidirectional"))
    )
    (net (code "78") (name "unconnected-(U1-ADC1_IN10{slash}PD4-Pad21)") (class "Default")
      (node (ref "U1") (pin "21") (pinfunction "ADC1_IN10/PD4_21") (pintype "bidirectional"))
    )
    (net (code "79") (name "unconnected-(U1-ADC1_IN11{slash}PB7-Pad20)") (class "Default")
      (node (ref "U1") (pin "20") (pinfunction "ADC1_IN11/PB7_20") (pintype "bidirectional"))
    )
    (net (code "80") (name "unconnected-(U1-ADC1_IN12{slash}PB6-Pad19)") (class "Default")
      (node (ref "U1") (pin "19") (pinfunction "ADC1_IN12/PB6_19") (pintype "bidirectional"))
    )
    (net (code "81") (name "unconnected-(U1-ADC1_IN13{slash}PB5-Pad18)") (class "Default")
      (node (ref "U1") (pin "18") (pinfunction "ADC1_IN13/PB5_18") (pintype "bidirectional"))
    )
    (net (code "82") (name "unconnected-(U1-COMP1_INP{slash}ADC1_IN15{slash}PB3-Pad16)") (class "Default")
      (node (ref "U1") (pin "16") (pinfunction "COMP1_INP/ADC1_IN15/PB3_16") (pintype "bidirectional"))
    )
    (net (code "83") (name "unconnected-(U2-FB{slash}NC-Pad15)") (class "Default")
      (node (ref "U2") (pin "15") (pinfunction "FB/NC_15") (pintype "bidirectional"))
    )
    (net (code "84") (name "unconnected-(U2-NC-Pad4)") (class "Default")
      (node (ref "U2") (pin "4") (pinfunction "NC_4") (pintype "no_connect"))
    )
    (net (code "85") (name "unconnected-(U2-NC-Pad8)") (class "Default")
      (node (ref "U2") (pin "8") (pinfunction "NC_8") (pintype "no_connect"))
    )
    (net (code "86") (name "unconnected-(U2-NC-Pad17)") (class "Default")
      (node (ref "U2") (pin "17") (pinfunction "NC_17") (pintype "no_connect"))
    )
    (net (code "87") (name "unconnected-(U2-NC-Pad18)") (class "Default")
      (node (ref "U2") (pin "18") (pinfunction "NC_18") (pintype "no_connect"))
    )
    (net (code "88") (name "unconnected-(X5-Pad1)") (class "Default")
      (node (ref "X5") (pin "1") (pinfunction "1_1") (pintype "passive"))
    )
    (net (code "89") (name "unconnected-(X5-Pad3)") (class "Default")
      (node (ref "X5") (pin "3") (pinfunction "3_3") (pintype "passive"))
    )
    (net (code "90") (name "unconnected-(X5-Pad11)") (class "Default")
      (node (ref "X5") (pin "11") (pinfunction "11_11") (pintype "passive"))
    )
    (net (code "91") (name "unconnected-(X5-Pad13)") (class "Default")
      (node (ref "X5") (pin "13") (pinfunction "13_13") (pintype "passive"))
    )
  )
)
